# CH579M-R1.net
KiCad netlist of a schematic drawn in Altium Designer
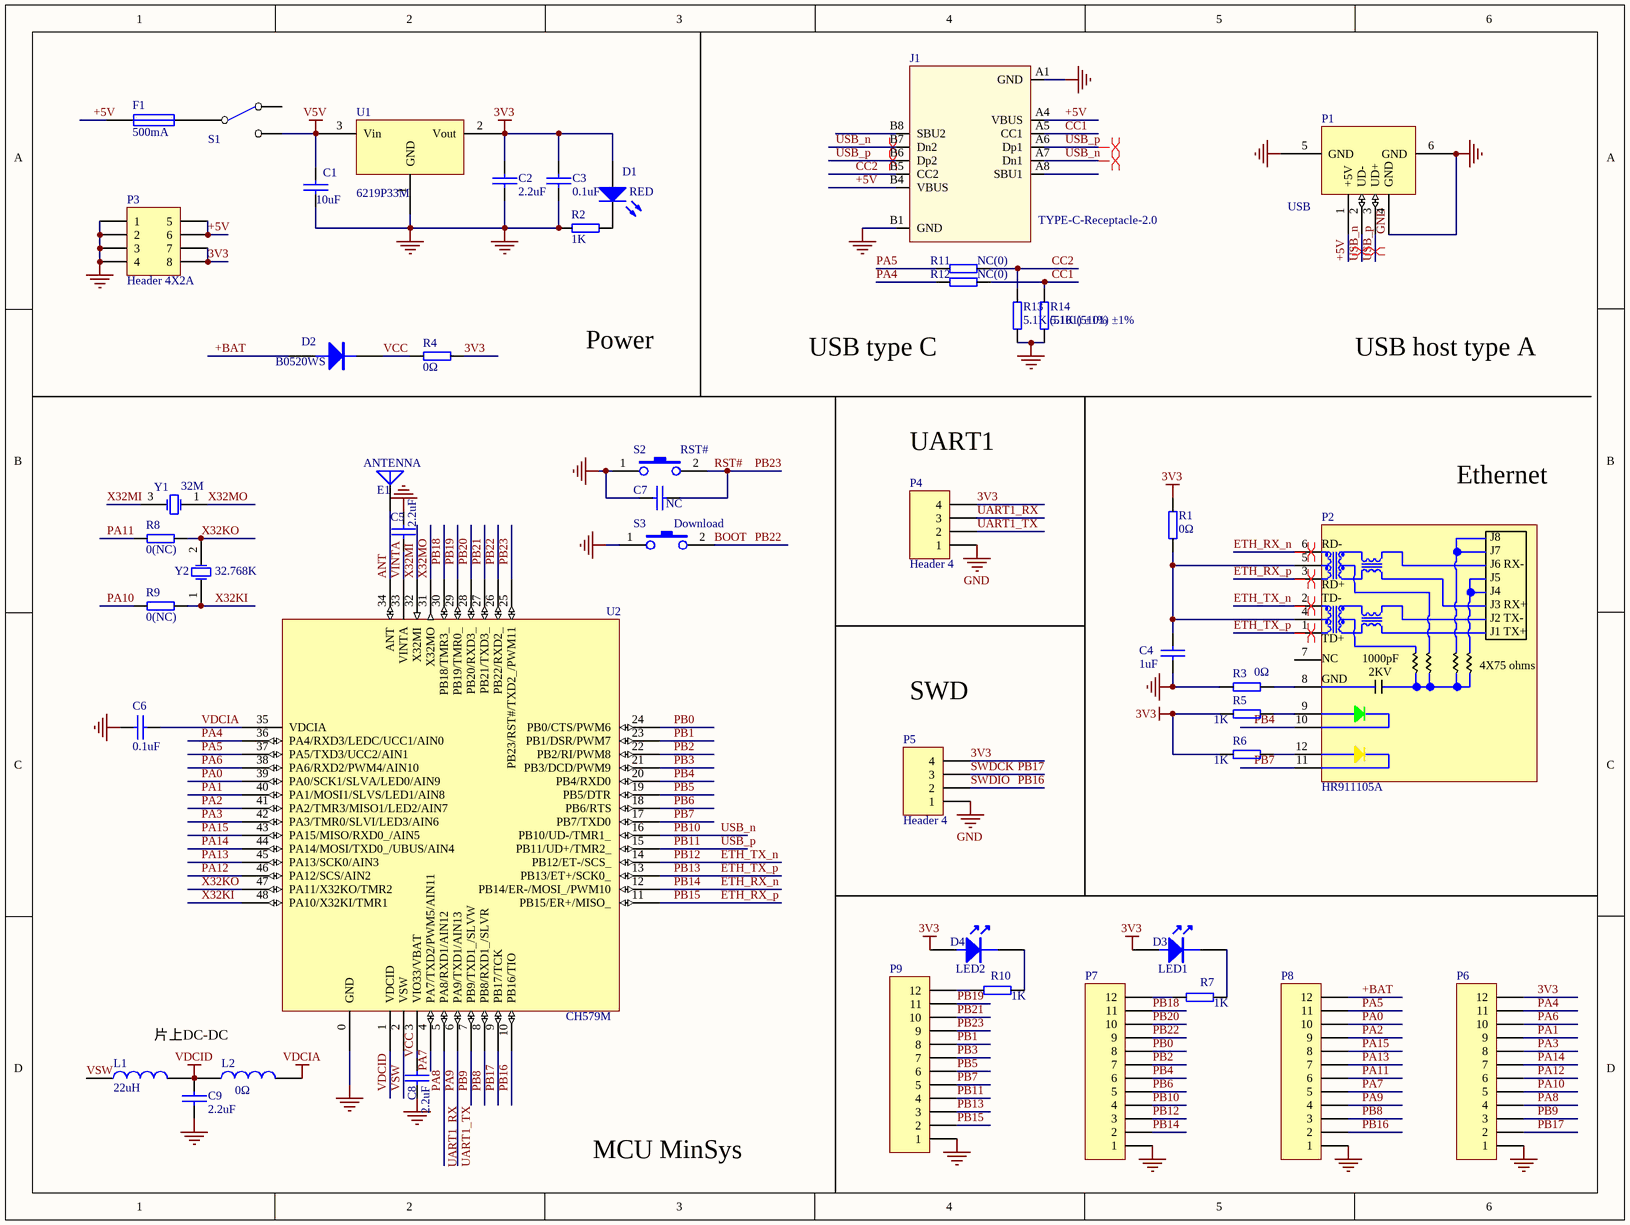
[diagram p0: CH579M-R1.SchDoc]

(export (version "E")
  (design (tool "Eeschema 10.0.6"))
  (components
    (comp (ref "C1")
      (value "10uF")
      (footprint "3216")
      (description "Capacitor")
      (libsource (lib "") (part "CAP_1"))
    )
    (comp (ref "C2")
      (value "2.2uF")
      (footprint "0603")
      (description "Capacitor")
      (libsource (lib "") (part "CAP_1"))
    )
    (comp (ref "C3")
      (value "0.1uF")
      (footprint "0603")
      (description "Capacitor")
      (libsource (lib "") (part "CAP_1"))
    )
    (comp (ref "C4")
      (value "1uF")
      (footprint "0603")
      (description "Capacitor")
      (libsource (lib "") (part "CAP_1"))
    )
    (comp (ref "C5")
      (value "2.2uF")
      (footprint "0603")
      (description "Capacitor")
      (libsource (lib "*") (part "CAP"))
    )
    (comp (ref "C6")
      (value "0.1uF")
      (footprint "0603")
      (description "Capacitor")
      (libsource (lib "*") (part "CAP"))
    )
    (comp (ref "C7")
      (value "NC")
      (footprint "0603")
      (description "Capacitor")
      (libsource (lib "*") (part "CAP"))
    )
    (comp (ref "C8")
      (value "2.2uF")
      (footprint "0603")
      (description "Capacitor")
      (libsource (lib "*") (part "CAP"))
    )
    (comp (ref "C9")
      (value "2.2uF")
      (footprint "0603")
      (description "Capacitor")
      (libsource (lib "*") (part "CAP"))
    )
    (comp (ref "D1")
      (value "RED")
      (footprint "0603+")
      (description "Typical INFRARED GaAs LED")
      (fields (field (name "PUBLISHER") "Altium Limited"))
      (libsource (lib "*") (part "LED0"))
    )
    (comp (ref "D2")
      (value "B0520WS")
      (footprint "SOD323")
      (description "Diode")
      (libsource (lib "*") (part "DIODE"))
    )
    (comp (ref "D3") (value "LED1") (footprint "0603+") (libsource (lib "*") (part "LED")))
    (comp (ref "D4") (value "LED2") (footprint "0603+") (libsource (lib "*") (part "LED")))
    (comp (ref "E1")
      (value "ANTENNA")
      (footprint "ANT-F-1-2.4G-1.6")
      (description "Generic Antenna")
      (libsource (lib "*") (part "ANTENNA"))
    )
    (comp (ref "F1")
      (value "500mA")
      (footprint "0805")
      (description "Fuse")
      (libsource (lib "wch_sch_others") (part "FUSE1"))
    )
    (comp (ref "J1")
      (value "TYPE-C-Receptacle-2.0")
      (footprint "TYPE-C-Receptacle-2.0")
      (description "Type-C USB2.0 母座")
      (libsource (lib "Miscellaneous SCH Lib") (part "TYPE-C-Receptacle-2.0"))
    )
    (comp (ref "L1") (value "22uH") (footprint "SMD-2.5*2*1.05") (libsource (lib "*") (part "INDUCTOR")))
    (comp (ref "L2") (value "0Ω") (footprint "0603") (libsource (lib "*") (part "INDUCTOR")))
    (comp (ref "P1")
      (value "USB")
      (footprint "USBA-L")
      (description "USB Port")
      (libsource (lib "*") (part "USB"))
    )
    (comp (ref "P2") (value "HR911105A") (footprint "HR911105A") (libsource (lib "*") (part "HR911105A")))
    (comp (ref "P3")
      (value "Header 4X2A")
      (footprint "IDC8")
      (description "Header, 4-Pin, Dual row")
      (fields (field (name "PUBLISHER") "Altium Limited"))
      (libsource (lib "Miscellaneous Connectors") (part "Header 4X2A"))
    )
    (comp (ref "P4")
      (value "Header 4")
      (footprint "HDR1X4")
      (description "Header, 4-Pin")
      (fields (field (name "PUBLISHER") "Altium Limited"))
      (libsource (lib "Miscellaneous Connectors") (part "Header 4"))
    )
    (comp (ref "P5")
      (value "Header 4")
      (footprint "HDR1X4")
      (description "Header, 4-Pin")
      (fields (field (name "PUBLISHER") "Altium Limited"))
      (libsource (lib "Miscellaneous Connectors") (part "Header 4"))
    )
    (comp (ref "P6")
      (value "Header 12")
      (footprint "SIP12 - 40mil")
      (description "Header, 12-Pin")
      (fields (field (name "PUBLISHER") "Altium Limited"))
      (libsource (lib "Miscellaneous Connectors") (part "Header 12"))
    )
    (comp (ref "P7")
      (value "Header 12")
      (footprint "SIP12 - 40mil")
      (description "Header, 12-Pin")
      (fields (field (name "PUBLISHER") "Altium Limited"))
      (libsource (lib "Miscellaneous Connectors") (part "Header 12"))
    )
    (comp (ref "P8")
      (value "Header 12")
      (footprint "SIP12 - 40mil")
      (description "Header, 12-Pin")
      (fields (field (name "PUBLISHER") "Altium Limited"))
      (libsource (lib "Miscellaneous Connectors") (part "Header 12"))
    )
    (comp (ref "P9")
      (value "Header 12")
      (footprint "SIP12 - 40mil")
      (description "Header, 12-Pin")
      (fields (field (name "PUBLISHER") "Altium Limited"))
      (libsource (lib "Miscellaneous Connectors") (part "Header 12"))
    )
    (comp (ref "R1") (value "0Ω") (footprint "0603") (libsource (lib "wch_sch_others") (part "RES")))
    (comp (ref "R2") (value "1K") (footprint "0603") (libsource (lib "wch_sch_others") (part "RES")))
    (comp (ref "R3") (value "0Ω") (footprint "0603") (libsource (lib "wch_sch_others") (part "RES")))
    (comp (ref "R4") (value "0Ω") (footprint "0603") (libsource (lib "wch_sch_others") (part "RES")))
    (comp (ref "R5") (value "1K") (footprint "0603") (libsource (lib "wch_sch_others") (part "RES")))
    (comp (ref "R6") (value "1K") (footprint "0603") (libsource (lib "wch_sch_others") (part "RES")))
    (comp (ref "R7") (value "1K") (footprint "0603") (libsource (lib "wch_sch_others") (part "RES")))
    (comp (ref "R8") (value "0(NC)") (footprint "0603") (libsource (lib "wch_sch_others") (part "RES")))
    (comp (ref "R9") (value "0(NC)") (footprint "0603") (libsource (lib "wch_sch_others") (part "RES")))
    (comp (ref "R10") (value "1K") (footprint "0603") (libsource (lib "wch_sch_others") (part "RES")))
    (comp (ref "R11") (value "NC(0)") (footprint "0603") (libsource (lib "wch_sch_others") (part "RES")))
    (comp (ref "R12") (value "NC(0)") (footprint "0603") (libsource (lib "wch_sch_others") (part "RES")))
    (comp (ref "R13")
      (value "5.1K (5101) ±1%")
      (footprint "0603")
      (libsource (lib "wch_sch_others") (part "RES"))
    )
    (comp (ref "R14")
      (value "5.1K (5101) ±1%")
      (footprint "0603")
      (libsource (lib "wch_sch_others") (part "RES"))
    )
    (comp (ref "S1") (value "SW SPDT") (footprint "KEY_B") (libsource (lib "*") (part "SW SPDT")))
    (comp (ref "S2")
      (value "RST#")
      (footprint "SMD_6.1x3.65x2.5mm-KEY")
      (libsource (lib "wch_sch_others") (part "KEY1"))
    )
    (comp (ref "S3")
      (value "Download")
      (footprint "SMD_6.1x3.65x2.5mm-KEY")
      (libsource (lib "wch_sch_others") (part "KEY1"))
    )
    (comp (ref "U1")
      (value "6219P33M")
      (footprint "SOT-23")
      (libsource (lib "wch_sch_others") (part "6219P33M"))
    )
    (comp (ref "U2")
      (value "CH579M")
      (footprint "QFN48_5X5")
      (description "ARM M0 MCU with BLE+Zigbee+Ethernet+USB")
      (libsource (lib "*") (part "CH579M"))
    )
    (comp (ref "Y1")
      (value "32M")
      (footprint "3225")
      (description "Crystal Oscillator")
      (fields (field (name "PUBLISHER") "Altium Limited"))
      (libsource (lib "*") (part "XTAL"))
    )
    (comp (ref "Y2")
      (value "32.768K")
      (footprint "fc-135")
      (description "Crystal Oscillator")
      (fields (field (name "PUBLISHER") "Altium Limited"))
      (libsource (lib "") (part "XTAL_1"))
    )
  )
  (nets
    (net (code "1") (name "/+5V") (class "Default")
      (node (ref "F1") (pin "1") (pinfunction "1_1") (pintype "passive"))
      (node (ref "J1") (pin "A4") (pinfunction "VBUS_A4") (pintype "passive"))
      (node (ref "J1") (pin "B4") (pinfunction "VBUS_B4") (pintype "passive"))
      (node (ref "P1") (pin "1") (pinfunction "+5V_1") (pintype "power_in"))
      (node (ref "P3") (pin "5") (pinfunction "5_5") (pintype "passive"))
      (node (ref "P3") (pin "6") (pinfunction "6_6") (pintype "passive"))
    )
    (net (code "2") (name "/+BAT") (class "Default")
      (node (ref "D2") (pin "1") (pinfunction "A_1") (pintype "passive"))
      (node (ref "P8") (pin "12") (pinfunction "12_12") (pintype "passive"))
    )
    (net (code "3") (name "/ANT") (class "Default")
      (node (ref "E1") (pin "1") (pinfunction "A_1") (pintype "passive"))
      (node (ref "U2") (pin "34") (pinfunction "ANT_34") (pintype "bidirectional"))
    )
    (net (code "4") (name "/BOOT") (class "Default")
      (node (ref "P7") (pin "9") (pinfunction "9_9") (pintype "passive"))
      (node (ref "S3") (pin "2") (pinfunction "2_2") (pintype "passive"))
      (node (ref "U2") (pin "26") (pinfunction "PB22/RXD2__26") (pintype "bidirectional"))
    )
    (net (code "5") (name "/CC1") (class "Default")
      (node (ref "J1") (pin "A5") (pinfunction "CC1_A5") (pintype "passive"))
      (node (ref "R12") (pin "2") (pintype "passive"))
      (node (ref "R14") (pin "1") (pintype "passive"))
    )
    (net (code "6") (name "/CC2") (class "Default")
      (node (ref "J1") (pin "B5") (pinfunction "CC2_B5") (pintype "passive"))
      (node (ref "R11") (pin "2") (pintype "passive"))
      (node (ref "R13") (pin "1") (pintype "passive"))
    )
    (net (code "7") (name "/ETH_RX_n") (class "Default")
      (node (ref "P2") (pin "6") (pintype "passive"))
      (node (ref "P7") (pin "2") (pinfunction "2_2") (pintype "passive"))
      (node (ref "U2") (pin "12") (pinfunction "PB14/ER-/MOSI_/PWM10_12") (pintype "bidirectional"))
    )
    (net (code "8") (name "/ETH_RX_p") (class "Default")
      (node (ref "P2") (pin "3") (pintype "passive"))
      (node (ref "P9") (pin "2") (pinfunction "2_2") (pintype "passive"))
      (node (ref "U2") (pin "11") (pinfunction "PB15/ER+/MISO__11") (pintype "bidirectional"))
    )
    (net (code "9") (name "/ETH_TX_n") (class "Default")
      (node (ref "P2") (pin "2") (pintype "passive"))
      (node (ref "P7") (pin "3") (pinfunction "3_3") (pintype "passive"))
      (node (ref "U2") (pin "14") (pinfunction "PB12/ET-/SCS__14") (pintype "bidirectional"))
    )
    (net (code "10") (name "/ETH_TX_p") (class "Default")
      (node (ref "P2") (pin "1") (pintype "passive"))
      (node (ref "P9") (pin "3") (pinfunction "3_3") (pintype "passive"))
      (node (ref "U2") (pin "13") (pinfunction "PB13/ET+/SCK0__13") (pintype "bidirectional"))
    )
    (net (code "11") (name "/PA0") (class "Default")
      (node (ref "P8") (pin "10") (pinfunction "10_10") (pintype "passive"))
      (node (ref "U2") (pin "39") (pinfunction "PA0/SCK1/SLVA/LED0/AIN9_39") (pintype "bidirectional"))
    )
    (net (code "12") (name "/PA1") (class "Default")
      (node (ref "P6") (pin "9") (pinfunction "9_9") (pintype "passive"))
      (node (ref "U2") (pin "40") (pinfunction "PA1/MOSI1/SLVS/LED1/AIN8_40") (pintype "bidirectional"))
    )
    (net (code "13") (name "/PA2") (class "Default")
      (node (ref "P8") (pin "9") (pinfunction "9_9") (pintype "passive"))
      (node (ref "U2") (pin "41") (pinfunction "PA2/TMR3/MISO1/LED2/AIN7_41") (pintype "bidirectional"))
    )
    (net (code "14") (name "/PA3") (class "Default")
      (node (ref "P6") (pin "8") (pinfunction "8_8") (pintype "passive"))
      (node (ref "U2") (pin "42") (pinfunction "PA3/TMR0/SLVI/LED3/AIN6_42") (pintype "bidirectional"))
    )
    (net (code "15") (name "/PA4") (class "Default")
      (node (ref "P6") (pin "11") (pinfunction "11_11") (pintype "passive"))
      (node (ref "R12") (pin "1") (pintype "passive"))
      (node (ref "U2") (pin "36") (pinfunction "PA4/RXD3/LEDC/UCC1/AIN0_36") (pintype "bidirectional"))
    )
    (net (code "16") (name "/PA5") (class "Default")
      (node (ref "P8") (pin "11") (pinfunction "11_11") (pintype "passive"))
      (node (ref "R11") (pin "1") (pintype "passive"))
      (node (ref "U2") (pin "37") (pinfunction "PA5/TXD3/UCC2/AIN1_37") (pintype "bidirectional"))
    )
    (net (code "17") (name "/PA6") (class "Default")
      (node (ref "P6") (pin "10") (pinfunction "10_10") (pintype "passive"))
      (node (ref "U2") (pin "38") (pinfunction "PA6/RXD2/PWM4/AIN10_38") (pintype "bidirectional"))
    )
    (net (code "18") (name "/PA7") (class "Default")
      (node (ref "P8") (pin "5") (pinfunction "5_5") (pintype "passive"))
      (node (ref "U2") (pin "4") (pinfunction "PA7/TXD2/PWM5/AIN11_4") (pintype "bidirectional"))
    )
    (net (code "19") (name "/PA8") (class "Default")
      (node (ref "P4") (pin "3") (pinfunction "3_3") (pintype "passive"))
      (node (ref "P6") (pin "4") (pinfunction "4_4") (pintype "passive"))
      (node (ref "U2") (pin "5") (pinfunction "PA8/RXD1/AIN12_5") (pintype "bidirectional"))
    )
    (net (code "20") (name "/PA9") (class "Default")
      (node (ref "P4") (pin "2") (pinfunction "2_2") (pintype "passive"))
      (node (ref "P8") (pin "4") (pinfunction "4_4") (pintype "passive"))
      (node (ref "U2") (pin "6") (pinfunction "PA9/TXD1/AIN13_6") (pintype "bidirectional"))
    )
    (net (code "21") (name "/PA10") (class "Default")
      (node (ref "P6") (pin "5") (pinfunction "5_5") (pintype "passive"))
      (node (ref "R9") (pin "1") (pintype "passive"))
    )
    (net (code "22") (name "/PA11") (class "Default")
      (node (ref "P8") (pin "6") (pinfunction "6_6") (pintype "passive"))
      (node (ref "R8") (pin "1") (pintype "passive"))
    )
    (net (code "23") (name "/PA12") (class "Default")
      (node (ref "P6") (pin "6") (pinfunction "6_6") (pintype "passive"))
      (node (ref "U2") (pin "46") (pinfunction "PA12/SCS/AIN2_46") (pintype "bidirectional"))
    )
    (net (code "24") (name "/PA13") (class "Default")
      (node (ref "P8") (pin "7") (pinfunction "7_7") (pintype "passive"))
      (node (ref "U2") (pin "45") (pinfunction "PA13/SCK0/AIN3_45") (pintype "bidirectional"))
    )
    (net (code "25") (name "/PA14") (class "Default")
      (node (ref "P6") (pin "7") (pinfunction "7_7") (pintype "passive"))
      (node (ref "U2") (pin "44") (pinfunction "PA14/MOSI/TXD0_/UBUS/AIN4_44") (pintype "bidirectional"))
    )
    (net (code "26") (name "/PA15") (class "Default")
      (node (ref "P8") (pin "8") (pinfunction "8_8") (pintype "passive"))
      (node (ref "U2") (pin "43") (pinfunction "PA15/MISO/RXD0_/AIN5_43") (pintype "bidirectional"))
    )
    (net (code "27") (name "/PB0") (class "Default")
      (node (ref "P7") (pin "8") (pinfunction "8_8") (pintype "passive"))
      (node (ref "U2") (pin "24") (pinfunction "PB0/CTS/PWM6_24") (pintype "bidirectional"))
    )
    (net (code "28") (name "/PB1") (class "Default")
      (node (ref "P9") (pin "8") (pinfunction "8_8") (pintype "passive"))
      (node (ref "U2") (pin "23") (pinfunction "PB1/DSR/PWM7_23") (pintype "bidirectional"))
    )
    (net (code "29") (name "/PB2") (class "Default")
      (node (ref "P7") (pin "7") (pinfunction "7_7") (pintype "passive"))
      (node (ref "U2") (pin "22") (pinfunction "PB2/RI/PWM8_22") (pintype "bidirectional"))
    )
    (net (code "30") (name "/PB3") (class "Default")
      (node (ref "P9") (pin "7") (pinfunction "7_7") (pintype "passive"))
      (node (ref "U2") (pin "21") (pinfunction "PB3/DCD/PWM9_21") (pintype "bidirectional"))
    )
    (net (code "31") (name "/PB4") (class "Default")
      (node (ref "P2") (pin "10") (pintype "passive"))
      (node (ref "P7") (pin "6") (pinfunction "6_6") (pintype "passive"))
      (node (ref "U2") (pin "20") (pinfunction "PB4/RXD0_20") (pintype "bidirectional"))
    )
    (net (code "32") (name "/PB5") (class "Default")
      (node (ref "P9") (pin "6") (pinfunction "6_6") (pintype "passive"))
      (node (ref "U2") (pin "19") (pinfunction "PB5/DTR_19") (pintype "bidirectional"))
    )
    (net (code "33") (name "/PB6") (class "Default")
      (node (ref "P7") (pin "5") (pinfunction "5_5") (pintype "passive"))
      (node (ref "U2") (pin "18") (pinfunction "PB6/RTS_18") (pintype "bidirectional"))
    )
    (net (code "34") (name "/PB7") (class "Default")
      (node (ref "P2") (pin "11") (pintype "passive"))
      (node (ref "P9") (pin "5") (pinfunction "5_5") (pintype "passive"))
      (node (ref "U2") (pin "17") (pinfunction "PB7/TXD0_17") (pintype "bidirectional"))
    )
    (net (code "35") (name "/PB8") (class "Default")
      (node (ref "P8") (pin "3") (pinfunction "3_3") (pintype "passive"))
      (node (ref "U2") (pin "8") (pinfunction "PB8/RXD1_/SLVR_8") (pintype "bidirectional"))
    )
    (net (code "36") (name "/PB9") (class "Default")
      (node (ref "P6") (pin "3") (pinfunction "3_3") (pintype "passive"))
      (node (ref "U2") (pin "7") (pinfunction "PB9/TXD1_/SLVW_7") (pintype "bidirectional"))
    )
    (net (code "37") (name "/PB10") (class "Default")
      (node (ref "J1") (pin "A7") (pinfunction "Dn1_A7") (pintype "passive"))
      (node (ref "J1") (pin "B7") (pinfunction "Dn2_B7") (pintype "passive"))
      (node (ref "P1") (pin "2") (pinfunction "UD-_2") (pintype "bidirectional"))
      (node (ref "P7") (pin "4") (pinfunction "4_4") (pintype "passive"))
      (node (ref "U2") (pin "16") (pinfunction "PB10/UD-/TMR1__16") (pintype "bidirectional"))
    )
    (net (code "38") (name "/PB11") (class "Default")
      (node (ref "J1") (pin "A6") (pinfunction "Dp1_A6") (pintype "passive"))
      (node (ref "J1") (pin "B6") (pinfunction "Dp2_B6") (pintype "passive"))
      (node (ref "P1") (pin "3") (pinfunction "UD+_3") (pintype "bidirectional"))
      (node (ref "P9") (pin "4") (pinfunction "4_4") (pintype "passive"))
      (node (ref "U2") (pin "15") (pinfunction "PB11/UD+/TMR2__15") (pintype "bidirectional"))
    )
    (net (code "39") (name "/PB16") (class "Default")
      (node (ref "P5") (pin "2") (pinfunction "2_2") (pintype "passive"))
      (node (ref "P8") (pin "2") (pinfunction "2_2") (pintype "passive"))
      (node (ref "U2") (pin "10") (pinfunction "PB16/TIO_10") (pintype "bidirectional"))
    )
    (net (code "40") (name "/PB17") (class "Default")
      (node (ref "P5") (pin "3") (pinfunction "3_3") (pintype "passive"))
      (node (ref "P6") (pin "2") (pinfunction "2_2") (pintype "passive"))
      (node (ref "U2") (pin "9") (pinfunction "PB17/TCK_9") (pintype "bidirectional"))
    )
    (net (code "41") (name "/PB18") (class "Default")
      (node (ref "P7") (pin "11") (pinfunction "11_11") (pintype "passive"))
      (node (ref "U2") (pin "30") (pinfunction "PB18/TMR3__30") (pintype "bidirectional"))
    )
    (net (code "42") (name "/PB19") (class "Default")
      (node (ref "P9") (pin "11") (pinfunction "11_11") (pintype "passive"))
      (node (ref "U2") (pin "29") (pinfunction "PB19/TMR0__29") (pintype "bidirectional"))
    )
    (net (code "43") (name "/PB20") (class "Default")
      (node (ref "P7") (pin "10") (pinfunction "10_10") (pintype "passive"))
      (node (ref "U2") (pin "28") (pinfunction "PB20/RXD3__28") (pintype "bidirectional"))
    )
    (net (code "44") (name "/PB21") (class "Default")
      (node (ref "P9") (pin "10") (pinfunction "10_10") (pintype "passive"))
      (node (ref "U2") (pin "27") (pinfunction "PB21/TXD3__27") (pintype "bidirectional"))
    )
    (net (code "45") (name "/PB23") (class "Default")
      (node (ref "C7") (pin "2") (pinfunction "2_2") (pintype "passive"))
      (node (ref "P9") (pin "9") (pinfunction "9_9") (pintype "passive"))
      (node (ref "S2") (pin "2") (pinfunction "2_2") (pintype "passive"))
      (node (ref "U2") (pin "25") (pinfunction "PB23/RST#/TXD2_/PWM11_25") (pintype "bidirectional"))
    )
    (net (code "46") (name "/VCC") (class "Default")
      (node (ref "C8") (pin "2") (pinfunction "2_2") (pintype "passive"))
      (node (ref "D2") (pin "2") (pinfunction "K_2") (pintype "passive"))
      (node (ref "R4") (pin "2") (pintype "passive"))
      (node (ref "U2") (pin "3") (pinfunction "VIO33/VBAT_3") (pintype "power_in"))
    )
    (net (code "47") (name "/VINTA") (class "Default")
      (node (ref "C5") (pin "1") (pinfunction "1_1") (pintype "passive"))
      (node (ref "U2") (pin "33") (pinfunction "VINTA_33") (pintype "power_in"))
    )
    (net (code "48") (name "/VSW") (class "Default")
      (node (ref "L1") (pin "1") (pinfunction "1_1") (pintype "passive"))
      (node (ref "U2") (pin "2") (pinfunction "VSW_2") (pintype "power_in"))
    )
    (net (code "49") (name "/X32KI") (class "Default")
      (node (ref "R9") (pin "2") (pintype "passive"))
      (node (ref "U2") (pin "48") (pinfunction "PA10/X32KI/TMR1_48") (pintype "bidirectional"))
      (node (ref "Y2") (pin "1") (pinfunction "OSC1_1") (pintype "passive"))
    )
    (net (code "50") (name "/X32KO") (class "Default")
      (node (ref "R8") (pin "2") (pintype "passive"))
      (node (ref "U2") (pin "47") (pinfunction "PA11/X32KO/TMR2_47") (pintype "bidirectional"))
      (node (ref "Y2") (pin "2") (pinfunction "OSC2_2") (pintype "passive"))
    )
    (net (code "51") (name "/X32MI") (class "Default")
      (node (ref "U2") (pin "32") (pinfunction "X32MI_32") (pintype "input"))
      (node (ref "Y1") (pin "3") (pinfunction "OSC2_3") (pintype "passive"))
    )
    (net (code "52") (name "/X32MO") (class "Default")
      (node (ref "U2") (pin "31") (pinfunction "X32MO_31") (pintype "output"))
      (node (ref "Y1") (pin "1") (pinfunction "OSC1_1") (pintype "passive"))
    )
    (net (code "53") (name "3V3") (class "Default")
      (node (ref "C2") (pin "1") (pinfunction "1_1") (pintype "passive"))
      (node (ref "C3") (pin "1") (pinfunction "1_1") (pintype "passive"))
      (node (ref "D1") (pin "1") (pinfunction "A_1") (pintype "passive"))
      (node (ref "D3") (pin "1") (pinfunction "1_1") (pintype "passive"))
      (node (ref "D4") (pin "1") (pinfunction "1_1") (pintype "passive"))
      (node (ref "P3") (pin "7") (pinfunction "7_7") (pintype "passive"))
      (node (ref "P3") (pin "8") (pinfunction "8_8") (pintype "passive"))
      (node (ref "P4") (pin "4") (pinfunction "4_4") (pintype "passive"))
      (node (ref "P5") (pin "4") (pinfunction "4_4") (pintype "passive"))
      (node (ref "P6") (pin "12") (pinfunction "12_12") (pintype "passive"))
      (node (ref "R1") (pin "2") (pintype "passive"))
      (node (ref "R4") (pin "1") (pintype "passive"))
      (node (ref "R5") (pin "1") (pintype "passive"))
      (node (ref "R6") (pin "1") (pintype "passive"))
      (node (ref "U1") (pin "2") (pinfunction "Vout_2") (pintype "passive"))
    )
    (net (code "54") (name "GND") (class "Default")
      (node (ref "C1") (pin "2") (pinfunction "2_2") (pintype "passive"))
      (node (ref "C2") (pin "2") (pinfunction "2_2") (pintype "passive"))
      (node (ref "C3") (pin "2") (pinfunction "2_2") (pintype "passive"))
      (node (ref "C4") (pin "1") (pinfunction "1_1") (pintype "passive"))
      (node (ref "C5") (pin "2") (pinfunction "2_2") (pintype "passive"))
      (node (ref "C6") (pin "2") (pinfunction "2_2") (pintype "passive"))
      (node (ref "C7") (pin "1") (pinfunction "1_1") (pintype "passive"))
      (node (ref "C8") (pin "1") (pinfunction "1_1") (pintype "passive"))
      (node (ref "C9") (pin "1") (pinfunction "1_1") (pintype "passive"))
      (node (ref "J1") (pin "A1") (pinfunction "GND_A1") (pintype "passive"))
      (node (ref "J1") (pin "B1") (pinfunction "GND_B1") (pintype "passive"))
      (node (ref "P1") (pin "4") (pinfunction "GND_4") (pintype "power_in"))
      (node (ref "P1") (pin "5") (pinfunction "GND_5") (pintype "power_in"))
      (node (ref "P1") (pin "6") (pinfunction "GND_6") (pintype "power_in"))
      (node (ref "P3") (pin "1") (pinfunction "1_1") (pintype "passive"))
      (node (ref "P3") (pin "2") (pinfunction "2_2") (pintype "passive"))
      (node (ref "P3") (pin "3") (pinfunction "3_3") (pintype "passive"))
      (node (ref "P3") (pin "4") (pinfunction "4_4") (pintype "passive"))
      (node (ref "P4") (pin "1") (pinfunction "1_1") (pintype "passive"))
      (node (ref "P5") (pin "1") (pinfunction "1_1") (pintype "passive"))
      (node (ref "P6") (pin "1") (pinfunction "1_1") (pintype "passive"))
      (node (ref "P7") (pin "1") (pinfunction "1_1") (pintype "passive"))
      (node (ref "P8") (pin "1") (pinfunction "1_1") (pintype "passive"))
      (node (ref "P9") (pin "1") (pinfunction "1_1") (pintype "passive"))
      (node (ref "R13") (pin "2") (pintype "passive"))
      (node (ref "R14") (pin "2") (pintype "passive"))
      (node (ref "R2") (pin "2") (pintype "passive"))
      (node (ref "R3") (pin "1") (pintype "passive"))
      (node (ref "S2") (pin "1") (pinfunction "1_1") (pintype "passive"))
      (node (ref "S3") (pin "1") (pinfunction "1_1") (pintype "passive"))
      (node (ref "U1") (pin "1") (pinfunction "GND_1") (pintype "passive"))
      (node (ref "U2") (pin "0") (pinfunction "GND_0") (pintype "power_in"))
    )
    (net (code "55") (name "Net-(C4-Pad2)") (class "Default")
      (node (ref "C4") (pin "2") (pinfunction "2_2") (pintype "passive"))
      (node (ref "P2") (pin "4") (pintype "passive"))
      (node (ref "P2") (pin "5") (pintype "passive"))
      (node (ref "R1") (pin "1") (pintype "passive"))
    )
    (net (code "56") (name "Net-(D1-K)") (class "Default")
      (node (ref "D1") (pin "2") (pinfunction "K_2") (pintype "passive"))
      (node (ref "R2") (pin "1") (pintype "passive"))
    )
    (net (code "57") (name "Net-(D3-Pad2)") (class "Default")
      (node (ref "D3") (pin "2") (pinfunction "2_2") (pintype "passive"))
      (node (ref "R7") (pin "2") (pintype "passive"))
    )
    (net (code "58") (name "Net-(D4-Pad2)") (class "Default")
      (node (ref "D4") (pin "2") (pinfunction "2_2") (pintype "passive"))
      (node (ref "R10") (pin "2") (pintype "passive"))
    )
    (net (code "59") (name "Net-(P2-Pad8)") (class "Default")
      (node (ref "P2") (pin "8") (pintype "passive"))
      (node (ref "R3") (pin "2") (pintype "passive"))
    )
    (net (code "60") (name "Net-(P2-Pad9)") (class "Default")
      (node (ref "P2") (pin "9") (pintype "passive"))
      (node (ref "R5") (pin "2") (pintype "passive"))
    )
    (net (code "61") (name "Net-(P2-Pad12)") (class "Default")
      (node (ref "P2") (pin "12") (pintype "passive"))
      (node (ref "R6") (pin "2") (pintype "passive"))
    )
    (net (code "62") (name "Net-(P7-Pad12)") (class "Default")
      (node (ref "P7") (pin "12") (pinfunction "12_12") (pintype "passive"))
      (node (ref "R7") (pin "1") (pintype "passive"))
    )
    (net (code "63") (name "Net-(P9-Pad12)") (class "Default")
      (node (ref "P9") (pin "12") (pinfunction "12_12") (pintype "passive"))
      (node (ref "R10") (pin "1") (pintype "passive"))
    )
    (net (code "64") (name "Net-(S1-COMMON)") (class "Default")
      (node (ref "F1") (pin "2") (pinfunction "2_2") (pintype "passive"))
      (node (ref "S1") (pin "1") (pinfunction "COMMON_1") (pintype "passive"))
    )
    (net (code "65") (name "V5V") (class "Default")
      (node (ref "C1") (pin "1") (pinfunction "1_1") (pintype "passive"))
      (node (ref "S1") (pin "2") (pinfunction "NC_2") (pintype "passive"))
      (node (ref "U1") (pin "3") (pinfunction "Vin_3") (pintype "passive"))
    )
    (net (code "66") (name "VDCIA") (class "Default")
      (node (ref "C6") (pin "1") (pinfunction "1_1") (pintype "passive"))
      (node (ref "L2") (pin "2") (pinfunction "2_2") (pintype "passive"))
      (node (ref "U2") (pin "35") (pinfunction "VDCIA_35") (pintype "power_in"))
    )
    (net (code "67") (name "VDCID") (class "Default")
      (node (ref "C9") (pin "2") (pinfunction "2_2") (pintype "passive"))
      (node (ref "L1") (pin "2") (pinfunction "2_2") (pintype "passive"))
      (node (ref "L2") (pin "1") (pinfunction "1_1") (pintype "passive"))
      (node (ref "U2") (pin "1") (pinfunction "VDCID_1") (pintype "power_in"))
    )
    (net (code "68") (name "unconnected-(J1-SBU1-PadA8)") (class "Default")
      (node (ref "J1") (pin "A8") (pinfunction "SBU1_A8") (pintype "passive"))
    )
    (net (code "69") (name "unconnected-(J1-SBU2-PadB8)") (class "Default")
      (node (ref "J1") (pin "B8") (pinfunction "SBU2_B8") (pintype "passive"))
    )
    (net (code "70") (name "unconnected-(P2-Pad7)") (class "Default")
      (node (ref "P2") (pin "7") (pintype "passive"))
    )
    (net (code "71") (name "unconnected-(S1-NO-Pad3)") (class "Default")
      (node (ref "S1") (pin "3") (pinfunction "NO_3") (pintype "passive"))
    )
  )
)
